# 2017_FDP_SCHEMA.net
KiCad netlist of a schematic drawn in Altium Designer
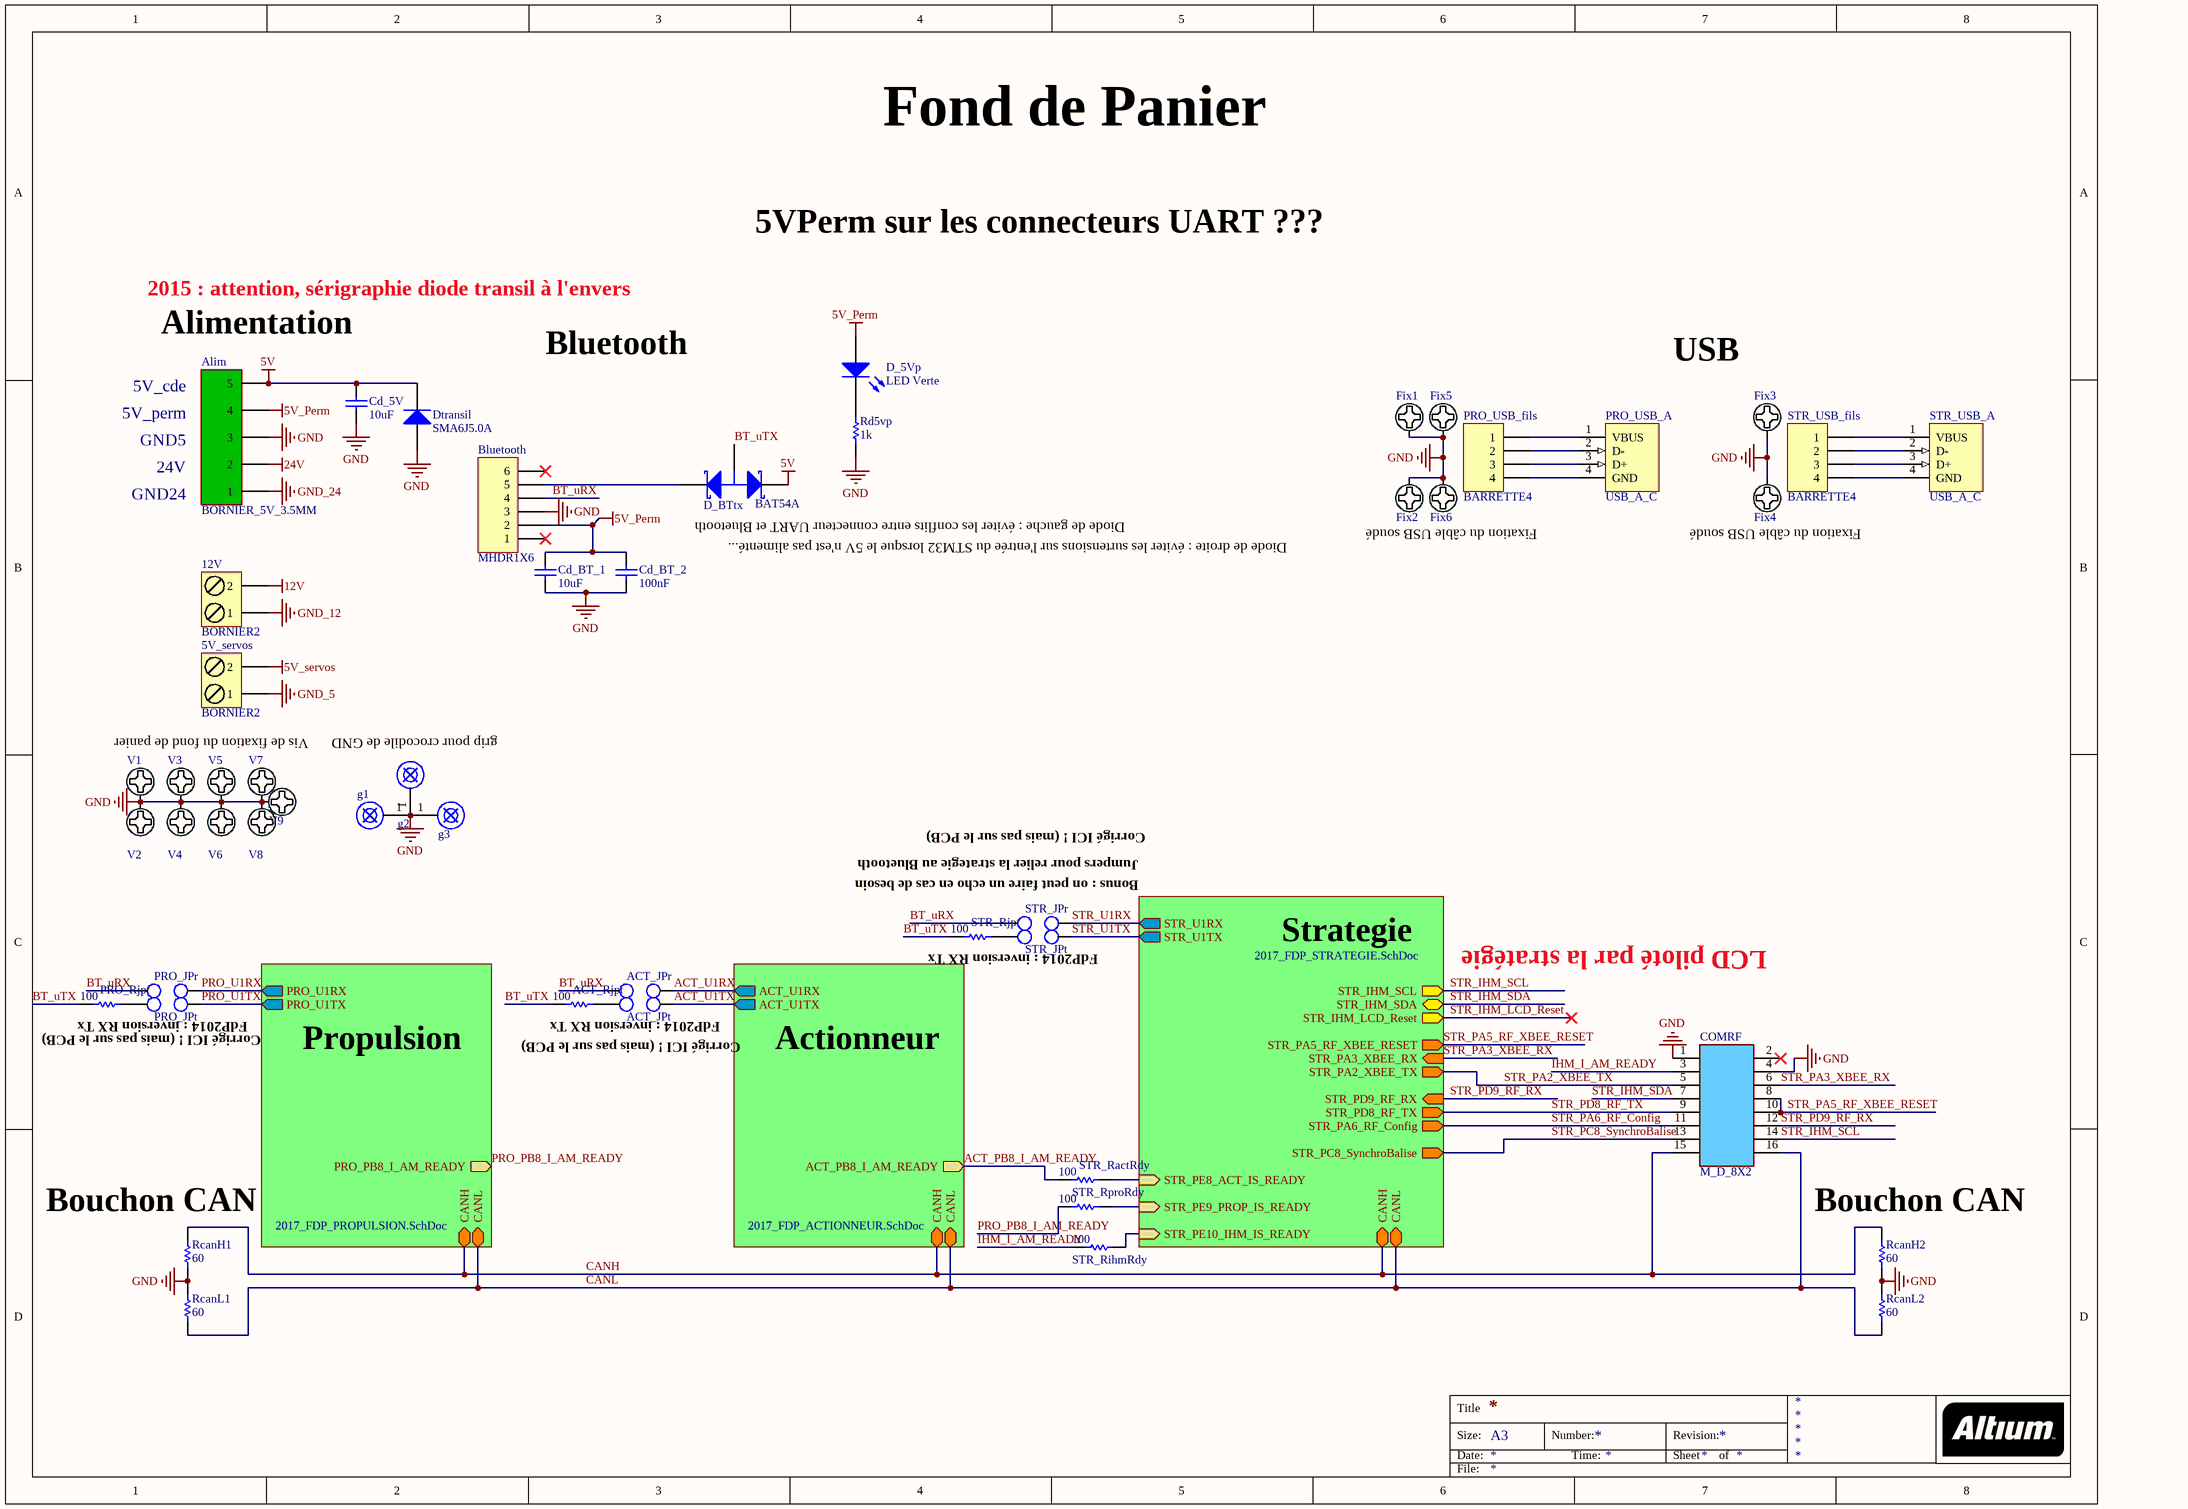
[diagram p0: 2017_FDP_SCHEMA.SchDoc]

(export (version "E")
  (design (tool "Eeschema 10.0.6"))
  (components
    (comp (ref "5V_servos")
      (value "BORNIER2")
      (footprint "BORNIER_2V_5.08MM")
      (description "Terminal blocks, 2 pins, pitch=5mm")
      (libsource (lib "Connecteur") (part "BORNIER2"))
    )
    (comp (ref "12V")
      (value "BORNIER2")
      (footprint "BORNIER_2V_5.08MM")
      (description "Terminal blocks, 2 pins, pitch=5mm")
      (libsource (lib "Connecteur") (part "BORNIER2"))
    )
    (comp (ref "ACT_JPr")
      (value "JUMPER2")
      (footprint "BARRETTE_2_M_D")
      (description "BARRETTE 2 CONTACTS 1 RANGEE MALE DROITE")
      (libsource (lib "connecteurs") (part "JUMPER2"))
    )
    (comp (ref "ACT_JPt")
      (value "JUMPER2")
      (footprint "BARRETTE_2_M_D")
      (description "BARRETTE 2 CONTACTS 1 RANGEE MALE DROITE")
      (libsource (lib "connecteurs") (part "JUMPER2"))
    )
    (comp (ref "ACT_Rjpt")
      (value "100")
      (footprint "R1206_N")
      (description "Resistor")
      (fields (field (name "PUBLISHER") "Altium Limited"))
      (libsource (lib "_ROBOT") (part "Resistor"))
    )
    (comp (ref "Alim")
      (value "BORNIER_5V_3.5MM")
      (footprint "BORNIER_5V_3.5MM_femelle_0")
      (libsource (lib "Connecteur") (part "BORNIER_5V_3.5MM"))
    )
    (comp (ref "Bluetooth")
      (value "MHDR1X6")
      (footprint "HE14_6")
      (description "Header, 6-Pin")
      (fields (field (name "PUBLISHER") "Altium Limited"))
      (libsource (lib "Miscellaneous Connectors") (part "MHDR1X6"))
    )
    (comp (ref "Cd_5V")
      (value "10uF")
      (footprint "C1206_N")
      (description "Capacitor")
      (fields (field (name "PUBLISHER") "Altium Limited"))
      (libsource (lib "_ROBOT") (part "Condensateur"))
    )
    (comp (ref "Cd_BT_1")
      (value "10uF")
      (footprint "C1206_N")
      (description "Capacitor")
      (fields (field (name "PUBLISHER") "Altium Limited"))
      (libsource (lib "_ROBOT") (part "Condensateur"))
    )
    (comp (ref "Cd_BT_2")
      (value "100nF")
      (footprint "C0805_N")
      (description "Capacitor")
      (fields (field (name "PUBLISHER") "Altium Limited"))
      (libsource (lib "_ROBOT") (part "Condensateur"))
    )
    (comp (ref "COMRF")
      (value "BARRETTE_8 CONTACTS_2 RANGEES_MALE_DROITE")
      (footprint "HE10/16_M_D_B P")
      (fields (field (name "TYPE") "M_D_8X2"))
      (libsource (lib "connecteurs") (part "BARRETTE_8 CONTACTS_2 RANGEES_MALE_DROITE"))
    )
    (comp (ref "Dtransil")
      (value "SMA6J5.0A")
      (footprint "DO214AC")
      (description "1 Amp General Purpose Rectifier")
      (fields (field (name "PUBLISHER") "Altium Limited"))
      (libsource (lib "Miscellaneous Devices") (part "Diode 1N4001"))
    )
    (comp (ref "D_5Vp")
      (value "LED Verte")
      (footprint "LED_0805")
      (description "Typical LED")
      (fields (field (name "PUBLISHER") "Altium Limited"))
      (libsource (lib "_ROBOT") (part "LED"))
    )
    (comp (ref "D_BTtx")
      (value "BAT54A")
      (footprint "SOT23-3N")
      (description "DIODE SCHOTTKY DOUBLE")
      (fields (field (name "MANUFACTURER") "ZETEX"))
      (libsource (lib "_ROBOT") (part "Diode Shottky double  BAT54A"))
    )
    (comp (ref "Fix1")
      (value "Pad_M3")
      (footprint "Point Test_D3_P1.6mm")
      (description "Vis M3 X 6mm _TORX_Tête 6mm")
      (fields (field (name "PUBLISHER") "Damien Guitton"))
      (libsource (lib "DG_Mecanique") (part "Vis M3 X 6mm _TORX_Tête 6mm"))
    )
    (comp (ref "Fix2")
      (value "Pad_M3")
      (footprint "Point Test_D3_P1.6mm")
      (description "Vis M3 X 6mm _TORX_Tête 6mm")
      (fields (field (name "PUBLISHER") "Damien Guitton"))
      (libsource (lib "DG_Mecanique") (part "Vis M3 X 6mm _TORX_Tête 6mm"))
    )
    (comp (ref "Fix3")
      (value "Pad_M3")
      (footprint "Point Test_D3_P1.6mm")
      (description "Vis M3 X 6mm _TORX_Tête 6mm")
      (fields (field (name "PUBLISHER") "Damien Guitton"))
      (libsource (lib "DG_Mecanique") (part "Vis M3 X 6mm _TORX_Tête 6mm"))
    )
    (comp (ref "Fix4")
      (value "Pad_M3")
      (footprint "Point Test_D3_P1.6mm")
      (description "Vis M3 X 6mm _TORX_Tête 6mm")
      (fields (field (name "PUBLISHER") "Damien Guitton"))
      (libsource (lib "DG_Mecanique") (part "Vis M3 X 6mm _TORX_Tête 6mm"))
    )
    (comp (ref "Fix5")
      (value "Pad_M3")
      (footprint "Point Test_D3_P1.6mm")
      (description "Vis M3 X 6mm _TORX_Tête 6mm")
      (fields (field (name "PUBLISHER") "Damien Guitton"))
      (libsource (lib "DG_Mecanique") (part "Vis M3 X 6mm _TORX_Tête 6mm"))
    )
    (comp (ref "Fix6")
      (value "Pad_M3")
      (footprint "Point Test_D3_P1.6mm")
      (description "Vis M3 X 6mm _TORX_Tête 6mm")
      (fields (field (name "PUBLISHER") "Damien Guitton"))
      (libsource (lib "DG_Mecanique") (part "Vis M3 X 6mm _TORX_Tête 6mm"))
    )
    (comp (ref "g1")
      (value "grip")
      (footprint "POINT_TEST")
      (description "POINT TEST")
      (libsource (lib "connecteurs") (part "POINT_TEST"))
    )
    (comp (ref "g2")
      (value "grip")
      (footprint "POINT_TEST")
      (description "POINT TEST")
      (libsource (lib "connecteurs") (part "POINT_TEST"))
    )
    (comp (ref "g3")
      (value "grip")
      (footprint "POINT_TEST")
      (description "POINT TEST")
      (libsource (lib "connecteurs") (part "POINT_TEST"))
    )
    (comp (ref "PRO_JPr")
      (value "JUMPER2")
      (footprint "BARRETTE_2_M_D")
      (description "BARRETTE 2 CONTACTS 1 RANGEE MALE DROITE")
      (libsource (lib "connecteurs") (part "JUMPER2"))
    )
    (comp (ref "PRO_JPt")
      (value "JUMPER2")
      (footprint "BARRETTE_2_M_D")
      (description "BARRETTE 2 CONTACTS 1 RANGEE MALE DROITE")
      (libsource (lib "connecteurs") (part "JUMPER2"))
    )
    (comp (ref "PRO_Rjpt")
      (value "100")
      (footprint "R1206_N")
      (description "Resistor")
      (fields (field (name "PUBLISHER") "Altium Limited"))
      (libsource (lib "_ROBOT") (part "Resistor"))
    )
    (comp (ref "PRO_USB_A")
      (value "USB_A_COUDEE")
      (footprint "USB_A_C")
      (description "EMBASE USB TRAVERSANTE TYPE A COUDEE")
      (fields (field (name "TYPE") "USB_A_C"))
      (libsource (lib "connecteurs") (part "USB_A_COUDEE"))
    )
    (comp (ref "PRO_USB_fils")
      (value "BARRETTE4")
      (footprint "HE14_4")
      (description "Header, 4-Pin")
      (fields (field (name "PUBLISHER") "Altium Limited"))
      (libsource (lib "Connecteur") (part "BARRETTE4"))
    )
    (comp (ref "RcanH1")
      (value "60")
      (footprint "R1206_N")
      (description "Resistor")
      (fields (field (name "PUBLISHER") "Altium Limited"))
      (libsource (lib "_ROBOT") (part "Resistor"))
    )
    (comp (ref "RcanH2")
      (value "60")
      (footprint "R1206_N")
      (description "Resistor")
      (fields (field (name "PUBLISHER") "Altium Limited"))
      (libsource (lib "_ROBOT") (part "Resistor"))
    )
    (comp (ref "RcanL1")
      (value "60")
      (footprint "R1206_N")
      (description "Resistor")
      (fields (field (name "PUBLISHER") "Altium Limited"))
      (libsource (lib "_ROBOT") (part "Resistor"))
    )
    (comp (ref "RcanL2")
      (value "60")
      (footprint "R1206_N")
      (description "Resistor")
      (fields (field (name "PUBLISHER") "Altium Limited"))
      (libsource (lib "_ROBOT") (part "Resistor"))
    )
    (comp (ref "Rd5vp")
      (value "1k")
      (footprint "R1206_N")
      (description "Resistor")
      (fields (field (name "PUBLISHER") "Altium Limited"))
      (libsource (lib "_ROBOT") (part "Resistor"))
    )
    (comp (ref "STR_JPr")
      (value "JUMPER2")
      (footprint "BARRETTE_2_M_D")
      (description "BARRETTE 2 CONTACTS 1 RANGEE MALE DROITE")
      (libsource (lib "connecteurs") (part "JUMPER2"))
    )
    (comp (ref "STR_JPt")
      (value "JUMPER2")
      (footprint "BARRETTE_2_M_D")
      (description "BARRETTE 2 CONTACTS 1 RANGEE MALE DROITE")
      (libsource (lib "connecteurs") (part "JUMPER2"))
    )
    (comp (ref "STR_RactRdy")
      (value "100")
      (footprint "R1206_N")
      (description "Resistor")
      (fields (field (name "PUBLISHER") "Altium Limited"))
      (libsource (lib "_ROBOT") (part "Resistor"))
    )
    (comp (ref "STR_RihmRdy")
      (value "100")
      (footprint "R1206_N")
      (description "Resistor")
      (fields (field (name "PUBLISHER") "Altium Limited"))
      (libsource (lib "_ROBOT") (part "Resistor"))
    )
    (comp (ref "STR_Rjpt")
      (value "100")
      (footprint "R1206_N")
      (description "Resistor")
      (fields (field (name "PUBLISHER") "Altium Limited"))
      (libsource (lib "_ROBOT") (part "Resistor"))
    )
    (comp (ref "STR_RproRdy")
      (value "100")
      (footprint "R1206_N")
      (description "Resistor")
      (fields (field (name "PUBLISHER") "Altium Limited"))
      (libsource (lib "_ROBOT") (part "Resistor"))
    )
    (comp (ref "STR_USB_A")
      (value "USB_A_COUDEE")
      (footprint "USB_A_C")
      (description "EMBASE USB TRAVERSANTE TYPE A COUDEE")
      (fields (field (name "TYPE") "USB_A_C"))
      (libsource (lib "connecteurs") (part "USB_A_COUDEE"))
    )
    (comp (ref "STR_USB_fils")
      (value "BARRETTE4")
      (footprint "HE14_4")
      (description "Header, 4-Pin")
      (fields (field (name "PUBLISHER") "Altium Limited"))
      (libsource (lib "Connecteur") (part "BARRETTE4"))
    )
    (comp (ref "V1")
      (value "Pad_M3")
      (footprint "M3x6mm Torx")
      (description "Vis M3 X 6mm _TORX_Tête 6mm")
      (fields (field (name "PUBLISHER") "Damien Guitton"))
      (libsource (lib "DG_Mecanique") (part "Vis M3 X 6mm _TORX_Tête 6mm"))
    )
    (comp (ref "V2")
      (value "Pad_M3")
      (footprint "M3x6mm Torx")
      (description "Vis M3 X 6mm _TORX_Tête 6mm")
      (fields (field (name "PUBLISHER") "Damien Guitton"))
      (libsource (lib "DG_Mecanique") (part "Vis M3 X 6mm _TORX_Tête 6mm"))
    )
    (comp (ref "V3")
      (value "Pad_M3")
      (footprint "M3x6mm Torx")
      (description "Vis M3 X 6mm _TORX_Tête 6mm")
      (fields (field (name "PUBLISHER") "Damien Guitton"))
      (libsource (lib "DG_Mecanique") (part "Vis M3 X 6mm _TORX_Tête 6mm"))
    )
    (comp (ref "V4")
      (value "Pad_M3")
      (footprint "M3x6mm Torx")
      (description "Vis M3 X 6mm _TORX_Tête 6mm")
      (fields (field (name "PUBLISHER") "Damien Guitton"))
      (libsource (lib "DG_Mecanique") (part "Vis M3 X 6mm _TORX_Tête 6mm"))
    )
    (comp (ref "V5")
      (value "Pad_M3")
      (footprint "M3x6mm Torx")
      (description "Vis M3 X 6mm _TORX_Tête 6mm")
      (fields (field (name "PUBLISHER") "Damien Guitton"))
      (libsource (lib "DG_Mecanique") (part "Vis M3 X 6mm _TORX_Tête 6mm"))
    )
    (comp (ref "V6")
      (value "Pad_M3")
      (footprint "M3x6mm Torx")
      (description "Vis M3 X 6mm _TORX_Tête 6mm")
      (fields (field (name "PUBLISHER") "Damien Guitton"))
      (libsource (lib "DG_Mecanique") (part "Vis M3 X 6mm _TORX_Tête 6mm"))
    )
    (comp (ref "V7")
      (value "Pad_M3")
      (footprint "M3x6mm Torx")
      (description "Vis M3 X 6mm _TORX_Tête 6mm")
      (fields (field (name "PUBLISHER") "Damien Guitton"))
      (libsource (lib "DG_Mecanique") (part "Vis M3 X 6mm _TORX_Tête 6mm"))
    )
    (comp (ref "V8")
      (value "Pad_M3")
      (footprint "M3x6mm Torx")
      (description "Vis M3 X 6mm _TORX_Tête 6mm")
      (fields (field (name "PUBLISHER") "Damien Guitton"))
      (libsource (lib "DG_Mecanique") (part "Vis M3 X 6mm _TORX_Tête 6mm"))
    )
    (comp (ref "V9")
      (value "Pad_M3")
      (footprint "M3x6mm Torx")
      (description "Vis M3 X 6mm _TORX_Tête 6mm")
      (fields (field (name "PUBLISHER") "Damien Guitton"))
      (libsource (lib "DG_Mecanique") (part "Vis M3 X 6mm _TORX_Tête 6mm"))
    )
  )
  (nets
    (net (code "1") (name "/ACT_PB8_I_AM_READY") (class "Default")
      (node (ref "STR_RactRdy") (pin "2") (pinfunction "2_2") (pintype "passive"))
    )
    (net (code "2") (name "/ACT_U1RX") (class "Default")
      (node (ref "ACT_JPr") (pin "2") (pinfunction "2_2") (pintype "passive"))
    )
    (net (code "3") (name "/ACT_U1TX") (class "Default")
      (node (ref "ACT_JPt") (pin "2") (pinfunction "2_2") (pintype "passive"))
    )
    (net (code "4") (name "/BT_uRX") (class "Default")
      (node (ref "ACT_JPr") (pin "1") (pinfunction "1_1") (pintype "passive"))
      (node (ref "Bluetooth") (pin "4") (pinfunction "4_4") (pintype "passive"))
      (node (ref "PRO_JPr") (pin "1") (pinfunction "1_1") (pintype "passive"))
      (node (ref "STR_JPr") (pin "1") (pinfunction "1_1") (pintype "passive"))
    )
    (net (code "5") (name "/BT_uTX") (class "Default")
      (node (ref "ACT_Rjpt") (pin "2") (pinfunction "2_2") (pintype "passive"))
      (node (ref "D_BTtx") (pin "3") (pinfunction "A_3") (pintype "passive"))
      (node (ref "PRO_Rjpt") (pin "2") (pinfunction "2_2") (pintype "passive"))
      (node (ref "STR_Rjpt") (pin "2") (pinfunction "2_2") (pintype "passive"))
    )
    (net (code "6") (name "/CANH") (class "Default")
      (node (ref "COMRF") (pin "15") (pinfunction "15_15") (pintype "passive"))
      (node (ref "RcanH1") (pin "2") (pinfunction "2_2") (pintype "passive"))
      (node (ref "RcanH2") (pin "1") (pinfunction "1_1") (pintype "passive"))
    )
    (net (code "7") (name "/CANL") (class "Default")
      (node (ref "COMRF") (pin "16") (pinfunction "16_16") (pintype "passive"))
      (node (ref "RcanL1") (pin "1") (pinfunction "1_1") (pintype "passive"))
      (node (ref "RcanL2") (pin "1") (pinfunction "1_1") (pintype "passive"))
    )
    (net (code "8") (name "/IHM_I_AM_READY") (class "Default")
      (node (ref "COMRF") (pin "3") (pinfunction "3_3") (pintype "passive"))
      (node (ref "STR_RihmRdy") (pin "2") (pinfunction "2_2") (pintype "passive"))
    )
    (net (code "9") (name "/PRO_PB8_I_AM_READY") (class "Default")
      (node (ref "STR_RproRdy") (pin "2") (pinfunction "2_2") (pintype "passive"))
    )
    (net (code "10") (name "/PRO_U1RX") (class "Default")
      (node (ref "PRO_JPr") (pin "2") (pinfunction "2_2") (pintype "passive"))
    )
    (net (code "11") (name "/PRO_U1TX") (class "Default")
      (node (ref "PRO_JPt") (pin "2") (pinfunction "2_2") (pintype "passive"))
    )
    (net (code "13") (name "/STR_IHM_SCL") (class "Default")
      (node (ref "COMRF") (pin "14") (pinfunction "14_14") (pintype "passive"))
    )
    (net (code "14") (name "/STR_IHM_SDA") (class "Default")
      (node (ref "COMRF") (pin "7") (pinfunction "7_7") (pintype "passive"))
    )
    (net (code "15") (name "/STR_PA2_XBEE_TX") (class "Default")
      (node (ref "COMRF") (pin "5") (pinfunction "5_5") (pintype "passive"))
    )
    (net (code "16") (name "/STR_PA3_XBEE_RX") (class "Default")
      (node (ref "COMRF") (pin "6") (pinfunction "6_6") (pintype "passive"))
    )
    (net (code "17") (name "/STR_PA5_RF_XBEE_RESET") (class "Default")
      (node (ref "COMRF") (pin "10") (pinfunction "10_10") (pintype "passive"))
      (node (ref "COMRF") (pin "8") (pinfunction "8_8") (pintype "passive"))
    )
    (net (code "18") (name "/STR_PA6_RF_Config") (class "Default")
      (node (ref "COMRF") (pin "11") (pinfunction "11_11") (pintype "passive"))
    )
    (net (code "19") (name "/STR_PC8_SynchroBalise") (class "Default")
      (node (ref "COMRF") (pin "13") (pinfunction "13_13") (pintype "passive"))
    )
    (net (code "20") (name "/STR_PD8_RF_TX") (class "Default")
      (node (ref "COMRF") (pin "9") (pinfunction "9_9") (pintype "passive"))
    )
    (net (code "21") (name "/STR_PD9_RF_RX") (class "Default")
      (node (ref "COMRF") (pin "12") (pinfunction "12_12") (pintype "passive"))
    )
    (net (code "22") (name "/STR_PE8_ACT_IS_READY") (class "Default")
      (node (ref "STR_RactRdy") (pin "1") (pinfunction "1_1") (pintype "passive"))
    )
    (net (code "23") (name "/STR_PE9_PROP_IS_READY") (class "Default")
      (node (ref "STR_RproRdy") (pin "1") (pinfunction "1_1") (pintype "passive"))
    )
    (net (code "24") (name "/STR_PE10_IHM_IS_READY") (class "Default")
      (node (ref "STR_RihmRdy") (pin "1") (pinfunction "1_1") (pintype "passive"))
    )
    (net (code "25") (name "/STR_U1RX") (class "Default")
      (node (ref "STR_JPr") (pin "2") (pinfunction "2_2") (pintype "passive"))
    )
    (net (code "26") (name "/STR_U1TX") (class "Default")
      (node (ref "STR_JPt") (pin "2") (pinfunction "2_2") (pintype "passive"))
    )
    (net (code "27") (name "5V") (class "Default")
      (node (ref "Alim") (pin "5") (pinfunction "5_5") (pintype "passive"))
      (node (ref "Cd_5V") (pin "2") (pinfunction "2_2") (pintype "passive"))
      (node (ref "D_BTtx") (pin "2") (pinfunction "K2_2") (pintype "passive"))
      (node (ref "Dtransil") (pin "2") (pinfunction "K_2") (pintype "passive"))
    )
    (net (code "28") (name "5V_Perm") (class "Default")
      (node (ref "Alim") (pin "4") (pinfunction "4_4") (pintype "passive"))
      (node (ref "Bluetooth") (pin "2") (pinfunction "2_2") (pintype "passive"))
      (node (ref "Cd_BT_1") (pin "2") (pinfunction "2_2") (pintype "passive"))
      (node (ref "Cd_BT_2") (pin "2") (pinfunction "2_2") (pintype "passive"))
      (node (ref "D_5Vp") (pin "1") (pinfunction "A_1") (pintype "passive"))
    )
    (net (code "29") (name "5V_servos") (class "Default")
      (node (ref "5V_servos") (pin "2") (pinfunction "2_2") (pintype "passive"))
    )
    (net (code "30") (name "12V") (class "Default")
      (node (ref "12V") (pin "2") (pinfunction "2_2") (pintype "passive"))
    )
    (net (code "31") (name "24V") (class "Default")
      (node (ref "Alim") (pin "2") (pinfunction "2_2") (pintype "passive"))
    )
    (net (code "32") (name "GND") (class "Default")
      (node (ref "Alim") (pin "3") (pinfunction "3_3") (pintype "passive"))
      (node (ref "Bluetooth") (pin "3") (pinfunction "3_3") (pintype "passive"))
      (node (ref "COMRF") (pin "1") (pinfunction "1_1") (pintype "passive"))
      (node (ref "COMRF") (pin "4") (pinfunction "4_4") (pintype "passive"))
      (node (ref "Cd_5V") (pin "1") (pinfunction "1_1") (pintype "passive"))
      (node (ref "Cd_BT_1") (pin "1") (pinfunction "1_1") (pintype "passive"))
      (node (ref "Cd_BT_2") (pin "1") (pinfunction "1_1") (pintype "passive"))
      (node (ref "Dtransil") (pin "1") (pinfunction "A_1") (pintype "passive"))
      (node (ref "Fix1") (pin "1") (pinfunction "1_1") (pintype "passive"))
      (node (ref "Fix2") (pin "1") (pinfunction "1_1") (pintype "passive"))
      (node (ref "Fix3") (pin "1") (pinfunction "1_1") (pintype "passive"))
      (node (ref "Fix4") (pin "1") (pinfunction "1_1") (pintype "passive"))
      (node (ref "Fix5") (pin "1") (pinfunction "1_1") (pintype "passive"))
      (node (ref "Fix6") (pin "1") (pinfunction "1_1") (pintype "passive"))
      (node (ref "RcanH1") (pin "1") (pinfunction "1_1") (pintype "passive"))
      (node (ref "RcanH2") (pin "2") (pinfunction "2_2") (pintype "passive"))
      (node (ref "RcanL1") (pin "2") (pinfunction "2_2") (pintype "passive"))
      (node (ref "RcanL2") (pin "2") (pinfunction "2_2") (pintype "passive"))
      (node (ref "Rd5vp") (pin "2") (pinfunction "2_2") (pintype "passive"))
      (node (ref "V1") (pin "1") (pinfunction "1_1") (pintype "passive"))
      (node (ref "V2") (pin "1") (pinfunction "1_1") (pintype "passive"))
      (node (ref "V3") (pin "1") (pinfunction "1_1") (pintype "passive"))
      (node (ref "V4") (pin "1") (pinfunction "1_1") (pintype "passive"))
      (node (ref "V5") (pin "1") (pinfunction "1_1") (pintype "passive"))
      (node (ref "V6") (pin "1") (pinfunction "1_1") (pintype "passive"))
      (node (ref "V7") (pin "1") (pinfunction "1_1") (pintype "passive"))
      (node (ref "V8") (pin "1") (pinfunction "1_1") (pintype "passive"))
      (node (ref "V9") (pin "1") (pinfunction "1_1") (pintype "passive"))
      (node (ref "g1") (pin "1") (pinfunction "3_1") (pintype "passive"))
      (node (ref "g2") (pin "1") (pinfunction "3_1") (pintype "passive"))
      (node (ref "g3") (pin "1") (pinfunction "3_1") (pintype "passive"))
    )
    (net (code "33") (name "GND_5") (class "Default")
      (node (ref "5V_servos") (pin "1") (pinfunction "1_1") (pintype "passive"))
    )
    (net (code "34") (name "GND_12") (class "Default")
      (node (ref "12V") (pin "1") (pinfunction "1_1") (pintype "passive"))
    )
    (net (code "35") (name "GND_24") (class "Default")
      (node (ref "Alim") (pin "1") (pinfunction "1_1") (pintype "passive"))
    )
    (net (code "36") (name "Net-(ACT_JPt-Pad1)") (class "Default")
      (node (ref "ACT_JPt") (pin "1") (pinfunction "1_1") (pintype "passive"))
      (node (ref "ACT_Rjpt") (pin "1") (pinfunction "1_1") (pintype "passive"))
    )
    (net (code "37") (name "Net-(D_5Vp-K)") (class "Default")
      (node (ref "D_5Vp") (pin "2") (pinfunction "K_2") (pintype "passive"))
      (node (ref "Rd5vp") (pin "1") (pinfunction "1_1") (pintype "passive"))
    )
    (net (code "38") (name "Net-(D_BTtx-K1)") (class "Default")
      (node (ref "Bluetooth") (pin "5") (pinfunction "5_5") (pintype "passive"))
      (node (ref "D_BTtx") (pin "1") (pinfunction "K1_1") (pintype "passive"))
    )
    (net (code "39") (name "Net-(PRO_JPt-Pad1)") (class "Default")
      (node (ref "PRO_JPt") (pin "1") (pinfunction "1_1") (pintype "passive"))
      (node (ref "PRO_Rjpt") (pin "1") (pinfunction "1_1") (pintype "passive"))
    )
    (net (code "40") (name "Net-(PRO_USB_A-D+)") (class "Default")
      (node (ref "PRO_USB_A") (pin "3") (pinfunction "D+_3") (pintype "input"))
      (node (ref "PRO_USB_fils") (pin "3") (pinfunction "3_3") (pintype "passive"))
    )
    (net (code "41") (name "Net-(PRO_USB_A-D-)") (class "Default")
      (node (ref "PRO_USB_A") (pin "2") (pinfunction "D-_2") (pintype "input"))
      (node (ref "PRO_USB_fils") (pin "2") (pinfunction "2_2") (pintype "passive"))
    )
    (net (code "42") (name "Net-(PRO_USB_A-GND)") (class "Default")
      (node (ref "PRO_USB_A") (pin "4") (pinfunction "GND_4") (pintype "power_in"))
      (node (ref "PRO_USB_fils") (pin "4") (pinfunction "4_4") (pintype "passive"))
    )
    (net (code "43") (name "Net-(PRO_USB_A-VBUS)") (class "Default")
      (node (ref "PRO_USB_A") (pin "1") (pinfunction "VBUS_1") (pintype "power_in"))
      (node (ref "PRO_USB_fils") (pin "1") (pinfunction "1_1") (pintype "passive"))
    )
    (net (code "44") (name "Net-(STR_JPt-Pad1)") (class "Default")
      (node (ref "STR_JPt") (pin "1") (pinfunction "1_1") (pintype "passive"))
      (node (ref "STR_Rjpt") (pin "1") (pinfunction "1_1") (pintype "passive"))
    )
    (net (code "45") (name "Net-(STR_USB_A-D+)") (class "Default")
      (node (ref "STR_USB_A") (pin "3") (pinfunction "D+_3") (pintype "input"))
      (node (ref "STR_USB_fils") (pin "3") (pinfunction "3_3") (pintype "passive"))
    )
    (net (code "46") (name "Net-(STR_USB_A-D-)") (class "Default")
      (node (ref "STR_USB_A") (pin "2") (pinfunction "D-_2") (pintype "input"))
      (node (ref "STR_USB_fils") (pin "2") (pinfunction "2_2") (pintype "passive"))
    )
    (net (code "47") (name "Net-(STR_USB_A-GND)") (class "Default")
      (node (ref "STR_USB_A") (pin "4") (pinfunction "GND_4") (pintype "power_in"))
      (node (ref "STR_USB_fils") (pin "4") (pinfunction "4_4") (pintype "passive"))
    )
    (net (code "48") (name "Net-(STR_USB_A-VBUS)") (class "Default")
      (node (ref "STR_USB_A") (pin "1") (pinfunction "VBUS_1") (pintype "power_in"))
      (node (ref "STR_USB_fils") (pin "1") (pinfunction "1_1") (pintype "passive"))
    )
    (net (code "49") (name "unconnected-(Bluetooth-Pad1)") (class "Default")
      (node (ref "Bluetooth") (pin "1") (pinfunction "1_1") (pintype "passive+no_connect"))
    )
    (net (code "50") (name "unconnected-(Bluetooth-Pad6)") (class "Default")
      (node (ref "Bluetooth") (pin "6") (pinfunction "6_6") (pintype "passive+no_connect"))
    )
    (net (code "51") (name "unconnected-(COMRF-Pad2)") (class "Default")
      (node (ref "COMRF") (pin "2") (pinfunction "2_2") (pintype "passive+no_connect"))
    )
  )
)
